# Breadboard_potentiometer_adapter_with_po.net
KiCad netlist of a schematic drawn in EasyEDA
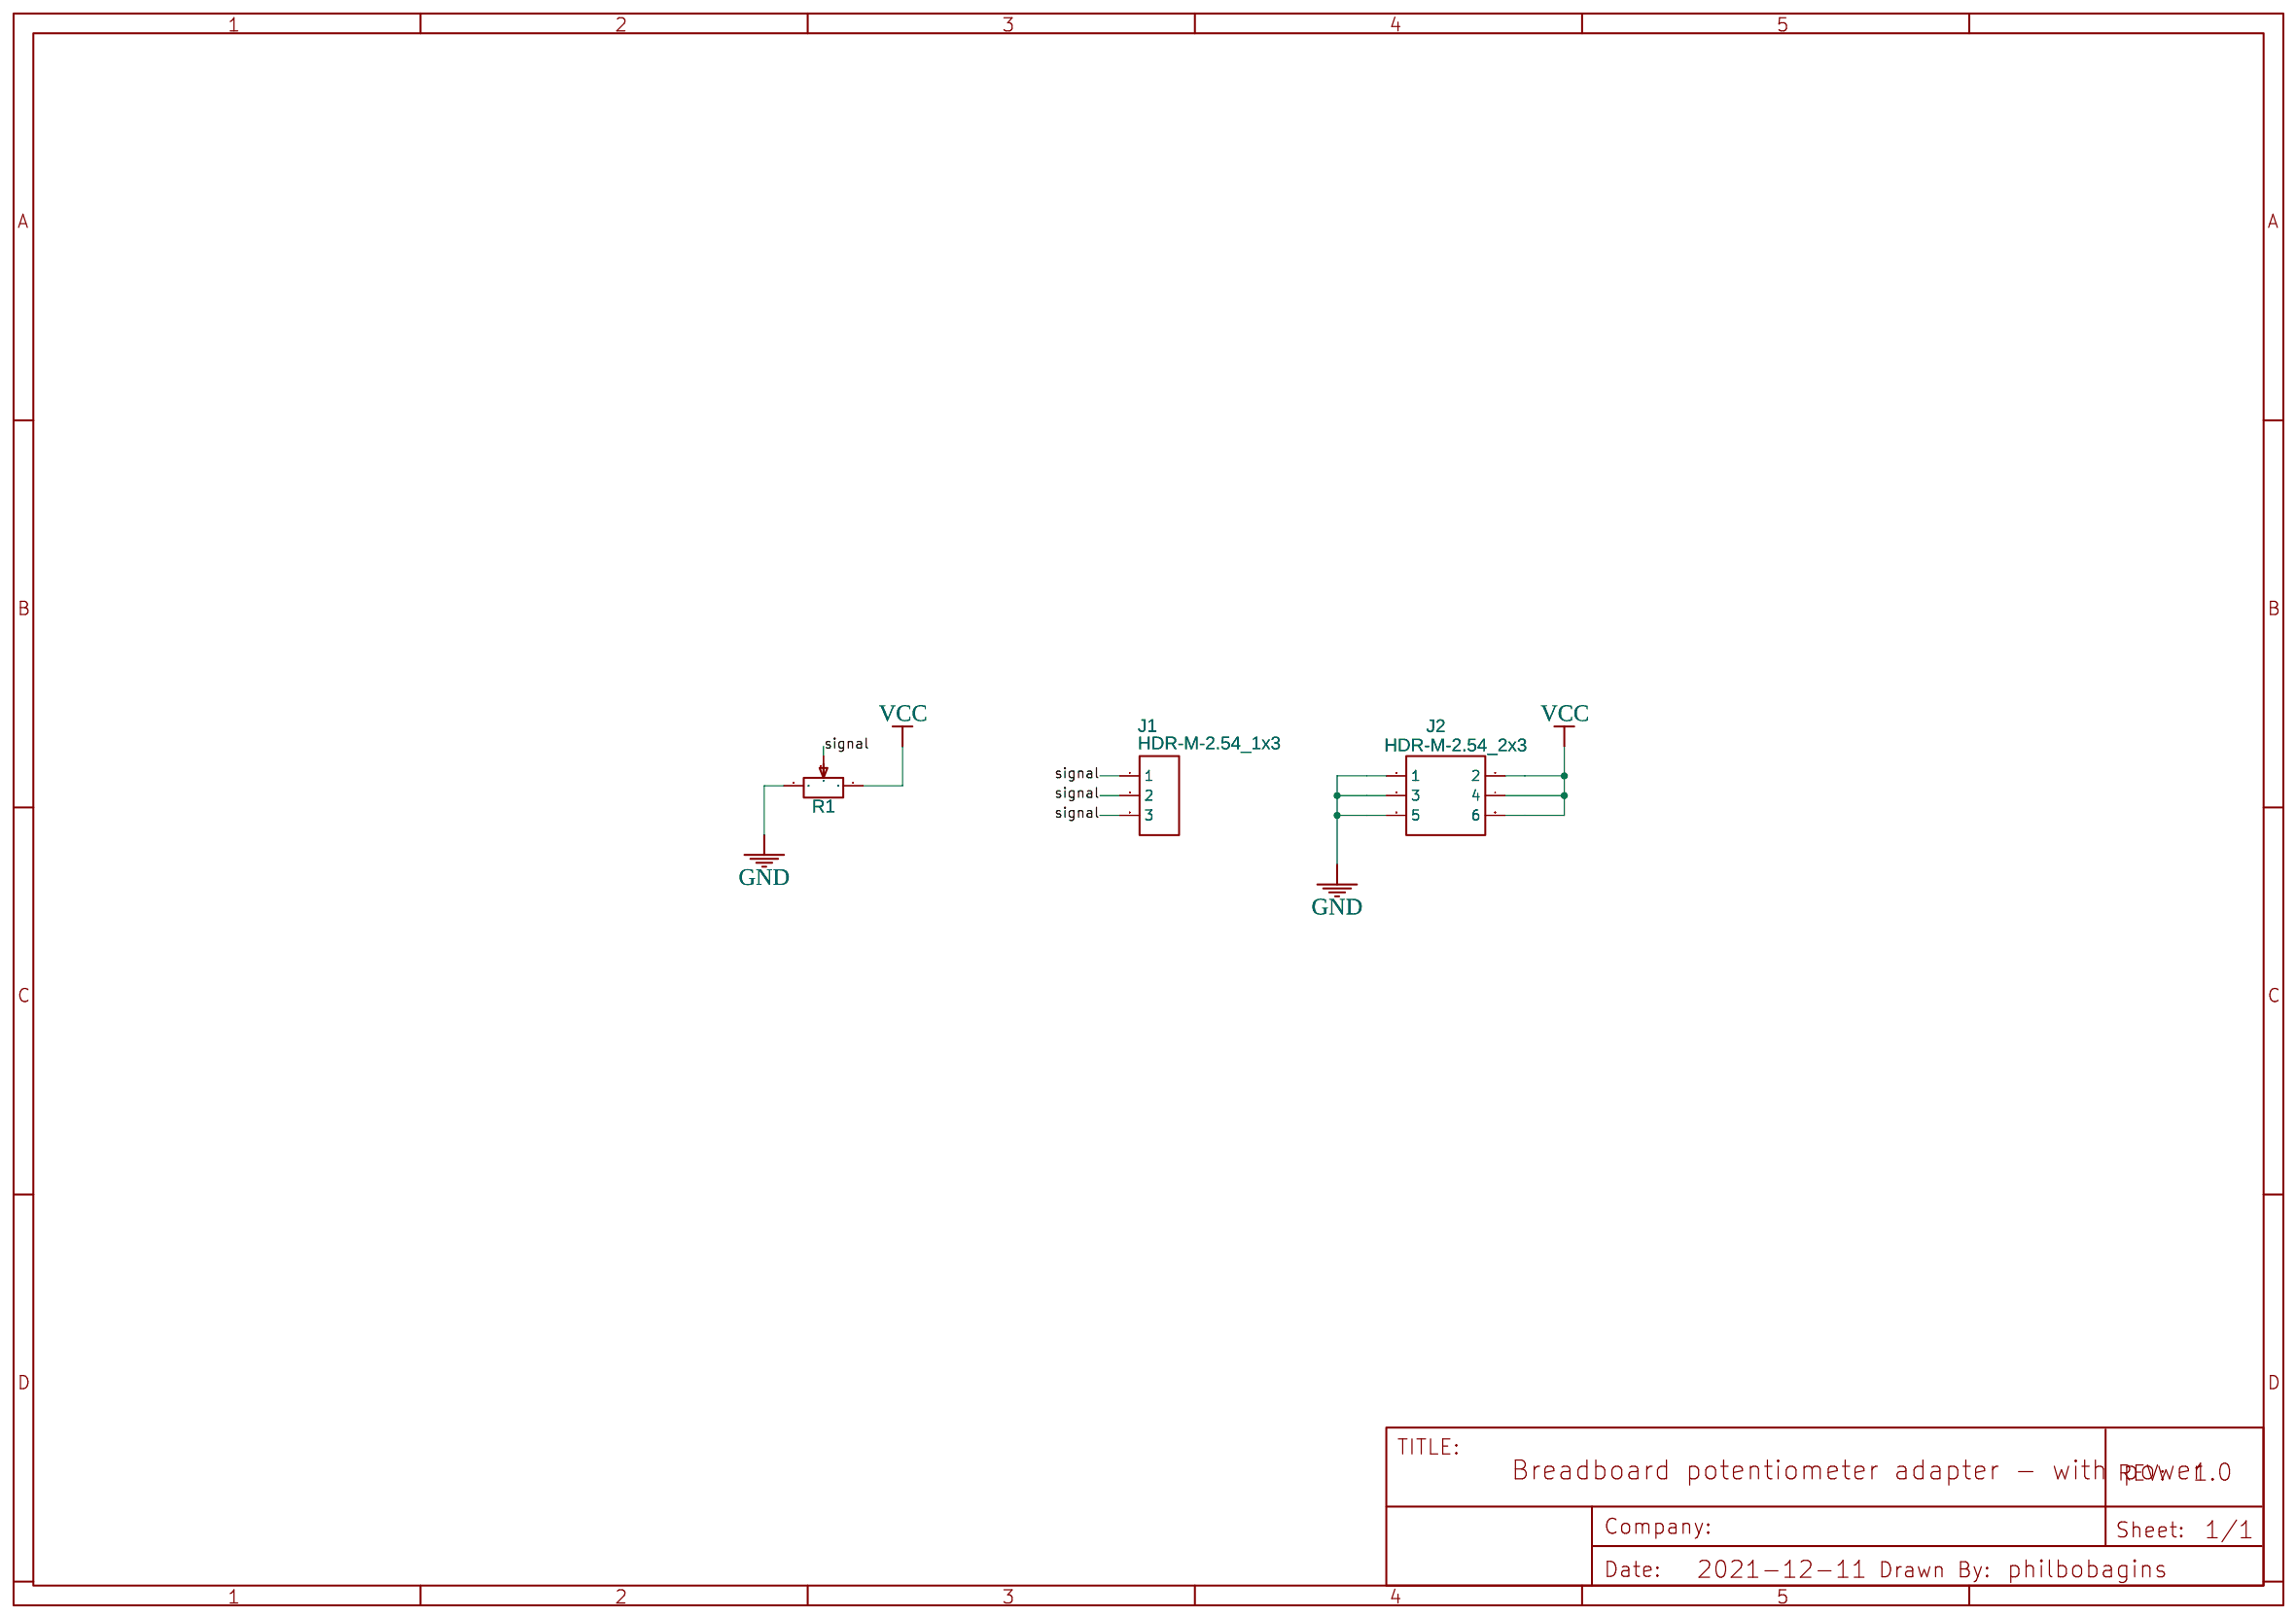
[diagram p0: schematic sheet]

(export (version "E")
  (design (tool "Eeschema 10.0.6"))
  (components
    (comp (ref "J1")
      (value "HDR-M-2.54_1x3")
      (fields (field (name "BOM_Supplier Part") "C180248"))
      (libsource (lib "") (part "HDR-M-2.54_1x3"))
    )
    (comp (ref "J2")
      (value "HDR-M-2.54_2x3")
      (fields (field (name "BOM_Supplier Part") "C65114"))
      (libsource (lib "") (part "HDR-M-2.54_2x3"))
    )
    (comp (ref "R1")
      (value "ALPS")
      (fields
        (field (name "BOM_Manufacturer Part") "RK1631110TT3")
        (field (name "BOM_Supplier Part") "C370977")
      )
      (libsource (lib "") (part "RK1631110TT3"))
    )
  )
  (nets
    (net (code "1") (name "/signal") (class "Default")
      (node (ref "J1") (pin "1") (pinfunction "1_1") (pintype "input"))
      (node (ref "J1") (pin "2") (pinfunction "2_2") (pintype "input"))
      (node (ref "J1") (pin "3") (pinfunction "3_3") (pintype "input"))
      (node (ref "R1") (pin "2") (pinfunction "2_2") (pintype "input"))
    )
    (net (code "2") (name "GND") (class "Default")
      (node (ref "J2") (pin "1") (pinfunction "1_1") (pintype "input"))
      (node (ref "J2") (pin "3") (pinfunction "3_3") (pintype "input"))
      (node (ref "J2") (pin "5") (pinfunction "5_5") (pintype "input"))
      (node (ref "R1") (pin "3") (pinfunction "3_3") (pintype "input"))
    )
    (net (code "3") (name "VCC") (class "Default")
      (node (ref "J2") (pin "2") (pinfunction "2_2") (pintype "input"))
      (node (ref "J2") (pin "4") (pinfunction "4_4") (pintype "input"))
      (node (ref "J2") (pin "6") (pinfunction "6_6") (pintype "input"))
      (node (ref "R1") (pin "1") (pinfunction "1_1") (pintype "input"))
    )
  )
)
